# Piezo.net
KiCad netlist of a schematic drawn in EAGLE
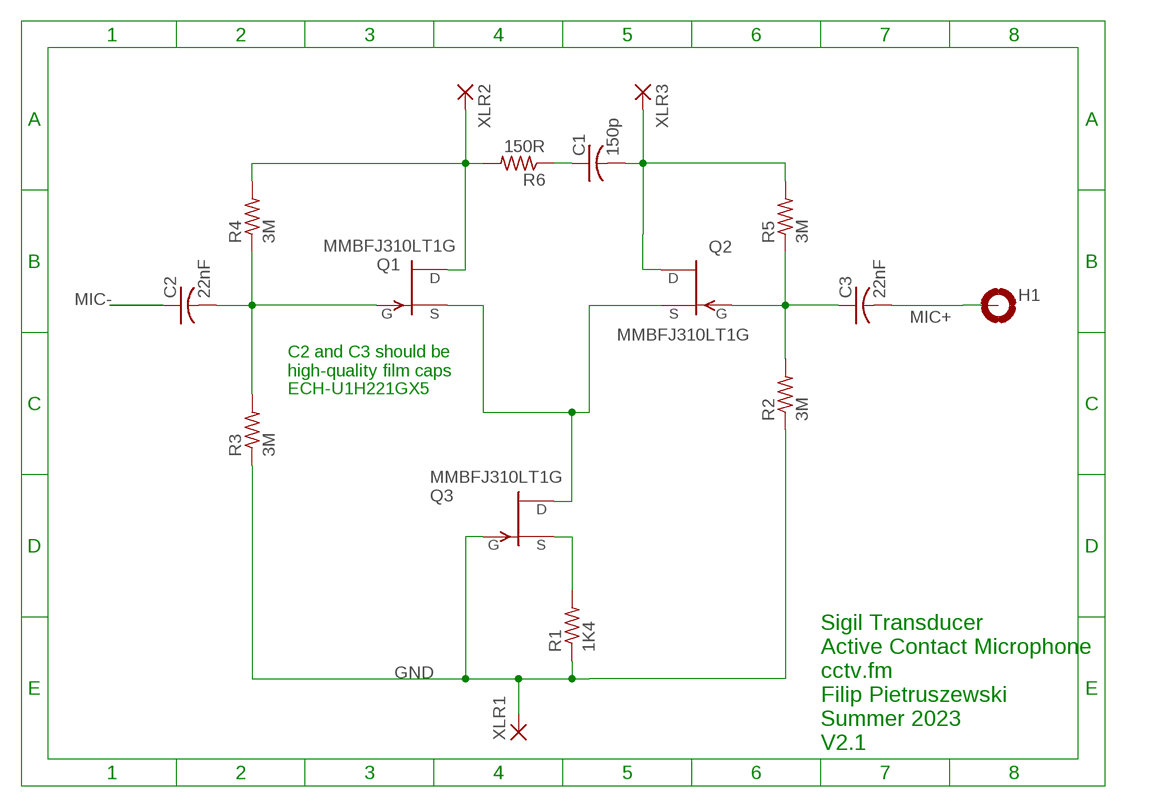
[diagram p0: schematic, sheet 1]

(export (version "E")
  (design (tool "Eeschema 10.0.6"))
  (components
    (comp (ref "C1")
      (value "150p")
      (footprint "eagle-import:C0805")
      (libsource (lib "eagle-import") (part "C-USC0805"))
    )
    (comp (ref "C2")
      (value "22nF")
      (footprint "eagle-import:C1206")
      (libsource (lib "eagle-import") (part "C-USC1206"))
    )
    (comp (ref "C3")
      (value "22nF")
      (footprint "eagle-import:C1206")
      (libsource (lib "eagle-import") (part "C-USC1206"))
    )
    (comp (ref "H1")
      (value "MOUNT-PAD-ROUND3.6")
      (footprint "eagle-import:3,6-PAD")
      (libsource (lib "eagle-import") (part "MOUNT-PAD-ROUND3.6"))
    )
    (comp (ref "Q1")
      (value "MMBFJ310LT1G")
      (footprint "eagle-import:SOT23")
      (libsource (lib "eagle-import") (part "?20SST1"))
    )
    (comp (ref "Q2")
      (value "MMBFJ310LT1G")
      (footprint "eagle-import:SOT23")
      (libsource (lib "eagle-import") (part "?20SST1"))
    )
    (comp (ref "Q3")
      (value "MMBFJ310LT1G")
      (footprint "eagle-import:SOT23")
      (libsource (lib "eagle-import") (part "?20SST1"))
    )
    (comp (ref "R1")
      (value "1K4")
      (footprint "eagle-import:R0805")
      (libsource (lib "eagle-import") (part "R-US_R0805"))
    )
    (comp (ref "R2")
      (value "3M")
      (footprint "eagle-import:R0805")
      (libsource (lib "eagle-import") (part "R-US_R0805"))
    )
    (comp (ref "R3")
      (value "3M")
      (footprint "eagle-import:R0805")
      (libsource (lib "eagle-import") (part "R-US_R0805"))
    )
    (comp (ref "R4")
      (value "3M")
      (footprint "eagle-import:R0805")
      (libsource (lib "eagle-import") (part "R-US_R0805"))
    )
    (comp (ref "R5")
      (value "3M")
      (footprint "eagle-import:R0805")
      (libsource (lib "eagle-import") (part "R-US_R0805"))
    )
    (comp (ref "R6")
      (value "150R")
      (footprint "eagle-import:R0805")
      (libsource (lib "eagle-import") (part "R-US_R0805"))
    )
    (comp (ref "XLR1")
      (value "DNP")
      (footprint "eagle-import:SMD2,54-5,08")
      (libsource (lib "eagle-import") (part "SMD5"))
    )
    (comp (ref "XLR2")
      (value "DNP")
      (footprint "eagle-import:SMD2,54-5,08")
      (libsource (lib "eagle-import") (part "SMD5"))
    )
    (comp (ref "XLR3")
      (value "DNP")
      (footprint "eagle-import:SMD2,54-5,08")
      (libsource (lib "eagle-import") (part "SMD5"))
    )
  )
  (nets
    (net (code "1") (name "/GND") (class "Default")
      (node (ref "Q3") (pin "3") (pinfunction "G_3") (pintype "passive"))
      (node (ref "R1") (pin "1") (pinfunction "1_1") (pintype "passive"))
      (node (ref "R2") (pin "1") (pinfunction "1_1") (pintype "passive"))
      (node (ref "R3") (pin "1") (pinfunction "1_1") (pintype "passive"))
      (node (ref "XLR1") (pin "1") (pinfunction "P_1") (pintype "passive"))
    )
    (net (code "2") (name "/MIC+") (class "Default")
      (node (ref "C3") (pin "2") (pinfunction "2_2") (pintype "passive"))
      (node (ref "H1") (pin "B3,6") (pinfunction "MOUNT_B3,6") (pintype "passive"))
    )
    (net (code "3") (name "/MIC-") (class "Default")
      (node (ref "C2") (pin "1") (pinfunction "1_1") (pintype "passive"))
    )
    (net (code "4") (name "Net-(C1-Pad1)") (class "Default")
      (node (ref "C1") (pin "1") (pinfunction "1_1") (pintype "passive"))
      (node (ref "R6") (pin "1") (pinfunction "1_1") (pintype "passive"))
    )
    (net (code "5") (name "Net-(Q1-D)") (class "Default")
      (node (ref "Q1") (pin "1") (pinfunction "D_1") (pintype "passive"))
      (node (ref "R4") (pin "2") (pinfunction "2_2") (pintype "passive"))
      (node (ref "R6") (pin "2") (pinfunction "2_2") (pintype "passive"))
      (node (ref "XLR2") (pin "1") (pinfunction "P_1") (pintype "passive"))
    )
    (net (code "6") (name "Net-(Q1-G)") (class "Default")
      (node (ref "C2") (pin "2") (pinfunction "2_2") (pintype "passive"))
      (node (ref "Q1") (pin "3") (pinfunction "G_3") (pintype "passive"))
      (node (ref "R3") (pin "2") (pinfunction "2_2") (pintype "passive"))
      (node (ref "R4") (pin "1") (pinfunction "1_1") (pintype "passive"))
    )
    (net (code "7") (name "Net-(Q1-S)") (class "Default")
      (node (ref "Q1") (pin "2") (pinfunction "S_2") (pintype "passive"))
      (node (ref "Q2") (pin "2") (pinfunction "S_2") (pintype "passive"))
      (node (ref "Q3") (pin "1") (pinfunction "D_1") (pintype "passive"))
    )
    (net (code "8") (name "Net-(Q2-D)") (class "Default")
      (node (ref "C1") (pin "2") (pinfunction "2_2") (pintype "passive"))
      (node (ref "Q2") (pin "1") (pinfunction "D_1") (pintype "passive"))
      (node (ref "R5") (pin "2") (pinfunction "2_2") (pintype "passive"))
      (node (ref "XLR3") (pin "1") (pinfunction "P_1") (pintype "passive"))
    )
    (net (code "9") (name "Net-(Q2-G)") (class "Default")
      (node (ref "C3") (pin "1") (pinfunction "1_1") (pintype "passive"))
      (node (ref "Q2") (pin "3") (pinfunction "G_3") (pintype "passive"))
      (node (ref "R2") (pin "2") (pinfunction "2_2") (pintype "passive"))
      (node (ref "R5") (pin "1") (pinfunction "1_1") (pintype "passive"))
    )
    (net (code "10") (name "Net-(Q3-S)") (class "Default")
      (node (ref "Q3") (pin "2") (pinfunction "S_2") (pintype "passive"))
      (node (ref "R1") (pin "2") (pinfunction "2_2") (pintype "passive"))
    )
  )
)
